# Fatar_Keyboard_TP8S_61Keys.net
KiCad netlist of a schematic drawn in EAGLE
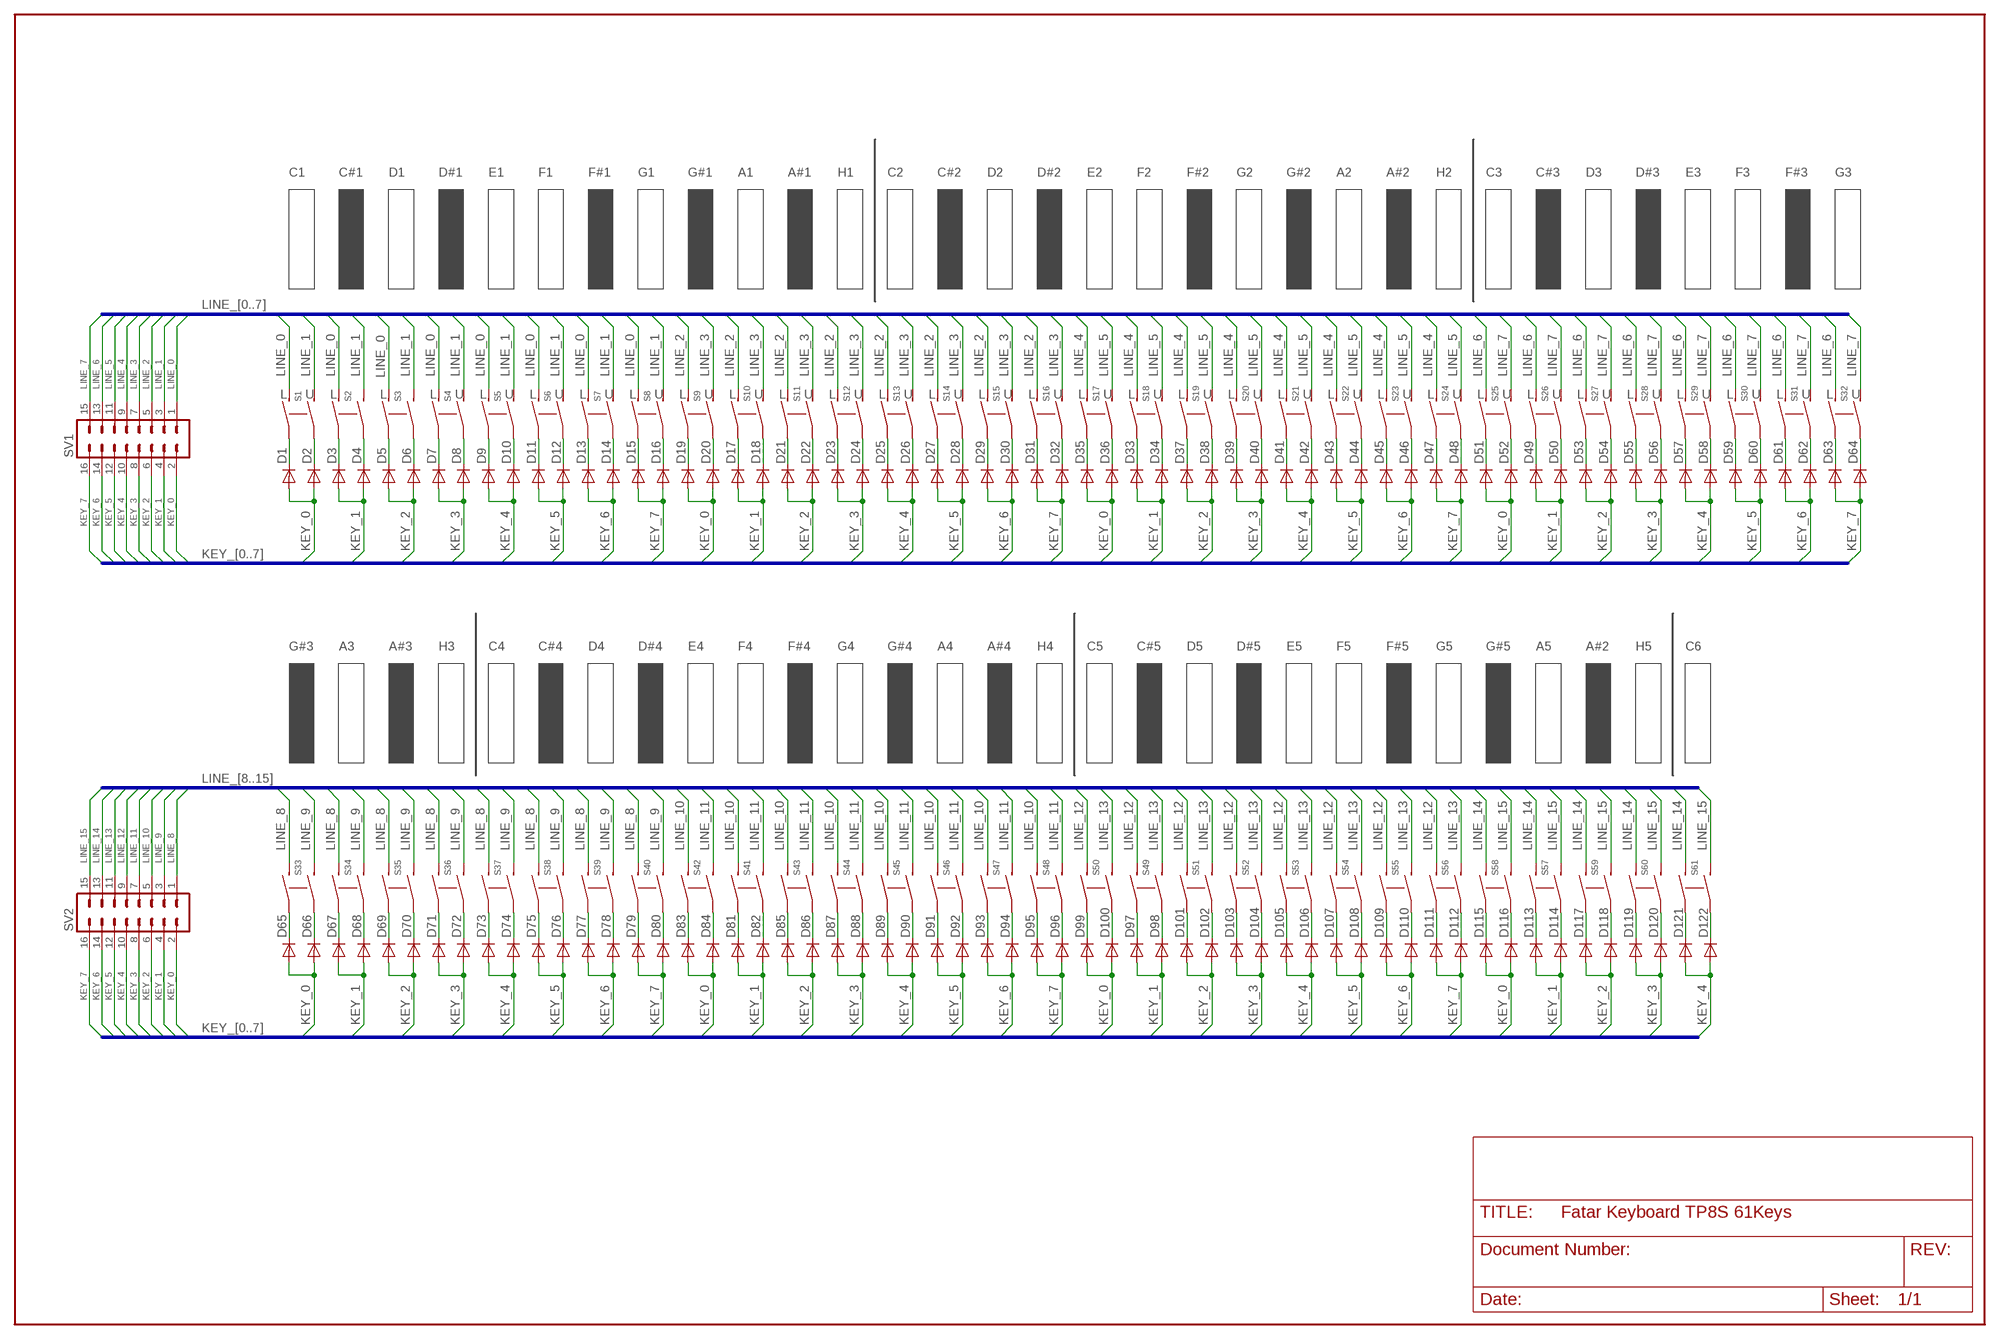
[diagram p0: schematic, sheet 1]

(export (version "E")
  (design (tool "Eeschema 10.0.6"))
  (components
    (comp (ref "D1")
      (value "1N4148DO35-7")
      (footprint "eagle-import:DO35-7")
      (libsource (lib "eagle-import") (part "1N4148DO35-7"))
    )
    (comp (ref "D2")
      (value "1N4148DO35-7")
      (footprint "eagle-import:DO35-7")
      (libsource (lib "eagle-import") (part "1N4148DO35-7"))
    )
    (comp (ref "D3")
      (value "1N4148DO35-7")
      (footprint "eagle-import:DO35-7")
      (libsource (lib "eagle-import") (part "1N4148DO35-7"))
    )
    (comp (ref "D4")
      (value "1N4148DO35-7")
      (footprint "eagle-import:DO35-7")
      (libsource (lib "eagle-import") (part "1N4148DO35-7"))
    )
    (comp (ref "D5")
      (value "1N4148DO35-7")
      (footprint "eagle-import:DO35-7")
      (libsource (lib "eagle-import") (part "1N4148DO35-7"))
    )
    (comp (ref "D6")
      (value "1N4148DO35-7")
      (footprint "eagle-import:DO35-7")
      (libsource (lib "eagle-import") (part "1N4148DO35-7"))
    )
    (comp (ref "D7")
      (value "1N4148DO35-7")
      (footprint "eagle-import:DO35-7")
      (libsource (lib "eagle-import") (part "1N4148DO35-7"))
    )
    (comp (ref "D8")
      (value "1N4148DO35-7")
      (footprint "eagle-import:DO35-7")
      (libsource (lib "eagle-import") (part "1N4148DO35-7"))
    )
    (comp (ref "D9")
      (value "1N4148DO35-7")
      (footprint "eagle-import:DO35-7")
      (libsource (lib "eagle-import") (part "1N4148DO35-7"))
    )
    (comp (ref "D10")
      (value "1N4148DO35-7")
      (footprint "eagle-import:DO35-7")
      (libsource (lib "eagle-import") (part "1N4148DO35-7"))
    )
    (comp (ref "D11")
      (value "1N4148DO35-7")
      (footprint "eagle-import:DO35-7")
      (libsource (lib "eagle-import") (part "1N4148DO35-7"))
    )
    (comp (ref "D12")
      (value "1N4148DO35-7")
      (footprint "eagle-import:DO35-7")
      (libsource (lib "eagle-import") (part "1N4148DO35-7"))
    )
    (comp (ref "D13")
      (value "1N4148DO35-7")
      (footprint "eagle-import:DO35-7")
      (libsource (lib "eagle-import") (part "1N4148DO35-7"))
    )
    (comp (ref "D14")
      (value "1N4148DO35-7")
      (footprint "eagle-import:DO35-7")
      (libsource (lib "eagle-import") (part "1N4148DO35-7"))
    )
    (comp (ref "D15")
      (value "1N4148DO35-7")
      (footprint "eagle-import:DO35-7")
      (libsource (lib "eagle-import") (part "1N4148DO35-7"))
    )
    (comp (ref "D16")
      (value "1N4148DO35-7")
      (footprint "eagle-import:DO35-7")
      (libsource (lib "eagle-import") (part "1N4148DO35-7"))
    )
    (comp (ref "D17")
      (value "1N4148DO35-7")
      (footprint "eagle-import:DO35-7")
      (libsource (lib "eagle-import") (part "1N4148DO35-7"))
    )
    (comp (ref "D18")
      (value "1N4148DO35-7")
      (footprint "eagle-import:DO35-7")
      (libsource (lib "eagle-import") (part "1N4148DO35-7"))
    )
    (comp (ref "D19")
      (value "1N4148DO35-7")
      (footprint "eagle-import:DO35-7")
      (libsource (lib "eagle-import") (part "1N4148DO35-7"))
    )
    (comp (ref "D20")
      (value "1N4148DO35-7")
      (footprint "eagle-import:DO35-7")
      (libsource (lib "eagle-import") (part "1N4148DO35-7"))
    )
    (comp (ref "D21")
      (value "1N4148DO35-7")
      (footprint "eagle-import:DO35-7")
      (libsource (lib "eagle-import") (part "1N4148DO35-7"))
    )
    (comp (ref "D22")
      (value "1N4148DO35-7")
      (footprint "eagle-import:DO35-7")
      (libsource (lib "eagle-import") (part "1N4148DO35-7"))
    )
    (comp (ref "D23")
      (value "1N4148DO35-7")
      (footprint "eagle-import:DO35-7")
      (libsource (lib "eagle-import") (part "1N4148DO35-7"))
    )
    (comp (ref "D24")
      (value "1N4148DO35-7")
      (footprint "eagle-import:DO35-7")
      (libsource (lib "eagle-import") (part "1N4148DO35-7"))
    )
    (comp (ref "D25")
      (value "1N4148DO35-7")
      (footprint "eagle-import:DO35-7")
      (libsource (lib "eagle-import") (part "1N4148DO35-7"))
    )
    (comp (ref "D26")
      (value "1N4148DO35-7")
      (footprint "eagle-import:DO35-7")
      (libsource (lib "eagle-import") (part "1N4148DO35-7"))
    )
    (comp (ref "D27")
      (value "1N4148DO35-7")
      (footprint "eagle-import:DO35-7")
      (libsource (lib "eagle-import") (part "1N4148DO35-7"))
    )
    (comp (ref "D28")
      (value "1N4148DO35-7")
      (footprint "eagle-import:DO35-7")
      (libsource (lib "eagle-import") (part "1N4148DO35-7"))
    )
    (comp (ref "D29")
      (value "1N4148DO35-7")
      (footprint "eagle-import:DO35-7")
      (libsource (lib "eagle-import") (part "1N4148DO35-7"))
    )
    (comp (ref "D30")
      (value "1N4148DO35-7")
      (footprint "eagle-import:DO35-7")
      (libsource (lib "eagle-import") (part "1N4148DO35-7"))
    )
    (comp (ref "D31")
      (value "1N4148DO35-7")
      (footprint "eagle-import:DO35-7")
      (libsource (lib "eagle-import") (part "1N4148DO35-7"))
    )
    (comp (ref "D32")
      (value "1N4148DO35-7")
      (footprint "eagle-import:DO35-7")
      (libsource (lib "eagle-import") (part "1N4148DO35-7"))
    )
    (comp (ref "D33")
      (value "1N4148DO35-7")
      (footprint "eagle-import:DO35-7")
      (libsource (lib "eagle-import") (part "1N4148DO35-7"))
    )
    (comp (ref "D34")
      (value "1N4148DO35-7")
      (footprint "eagle-import:DO35-7")
      (libsource (lib "eagle-import") (part "1N4148DO35-7"))
    )
    (comp (ref "D35")
      (value "1N4148DO35-7")
      (footprint "eagle-import:DO35-7")
      (libsource (lib "eagle-import") (part "1N4148DO35-7"))
    )
    (comp (ref "D36")
      (value "1N4148DO35-7")
      (footprint "eagle-import:DO35-7")
      (libsource (lib "eagle-import") (part "1N4148DO35-7"))
    )
    (comp (ref "D37")
      (value "1N4148DO35-7")
      (footprint "eagle-import:DO35-7")
      (libsource (lib "eagle-import") (part "1N4148DO35-7"))
    )
    (comp (ref "D38")
      (value "1N4148DO35-7")
      (footprint "eagle-import:DO35-7")
      (libsource (lib "eagle-import") (part "1N4148DO35-7"))
    )
    (comp (ref "D39")
      (value "1N4148DO35-7")
      (footprint "eagle-import:DO35-7")
      (libsource (lib "eagle-import") (part "1N4148DO35-7"))
    )
    (comp (ref "D40")
      (value "1N4148DO35-7")
      (footprint "eagle-import:DO35-7")
      (libsource (lib "eagle-import") (part "1N4148DO35-7"))
    )
    (comp (ref "D41")
      (value "1N4148DO35-7")
      (footprint "eagle-import:DO35-7")
      (libsource (lib "eagle-import") (part "1N4148DO35-7"))
    )
    (comp (ref "D42")
      (value "1N4148DO35-7")
      (footprint "eagle-import:DO35-7")
      (libsource (lib "eagle-import") (part "1N4148DO35-7"))
    )
    (comp (ref "D43")
      (value "1N4148DO35-7")
      (footprint "eagle-import:DO35-7")
      (libsource (lib "eagle-import") (part "1N4148DO35-7"))
    )
    (comp (ref "D44")
      (value "1N4148DO35-7")
      (footprint "eagle-import:DO35-7")
      (libsource (lib "eagle-import") (part "1N4148DO35-7"))
    )
    (comp (ref "D45")
      (value "1N4148DO35-7")
      (footprint "eagle-import:DO35-7")
      (libsource (lib "eagle-import") (part "1N4148DO35-7"))
    )
    (comp (ref "D46")
      (value "1N4148DO35-7")
      (footprint "eagle-import:DO35-7")
      (libsource (lib "eagle-import") (part "1N4148DO35-7"))
    )
    (comp (ref "D47")
      (value "1N4148DO35-7")
      (footprint "eagle-import:DO35-7")
      (libsource (lib "eagle-import") (part "1N4148DO35-7"))
    )
    (comp (ref "D48")
      (value "1N4148DO35-7")
      (footprint "eagle-import:DO35-7")
      (libsource (lib "eagle-import") (part "1N4148DO35-7"))
    )
    (comp (ref "D49")
      (value "1N4148DO35-7")
      (footprint "eagle-import:DO35-7")
      (libsource (lib "eagle-import") (part "1N4148DO35-7"))
    )
    (comp (ref "D50")
      (value "1N4148DO35-7")
      (footprint "eagle-import:DO35-7")
      (libsource (lib "eagle-import") (part "1N4148DO35-7"))
    )
    (comp (ref "D51")
      (value "1N4148DO35-7")
      (footprint "eagle-import:DO35-7")
      (libsource (lib "eagle-import") (part "1N4148DO35-7"))
    )
    (comp (ref "D52")
      (value "1N4148DO35-7")
      (footprint "eagle-import:DO35-7")
      (libsource (lib "eagle-import") (part "1N4148DO35-7"))
    )
    (comp (ref "D53")
      (value "1N4148DO35-7")
      (footprint "eagle-import:DO35-7")
      (libsource (lib "eagle-import") (part "1N4148DO35-7"))
    )
    (comp (ref "D54")
      (value "1N4148DO35-7")
      (footprint "eagle-import:DO35-7")
      (libsource (lib "eagle-import") (part "1N4148DO35-7"))
    )
    (comp (ref "D55")
      (value "1N4148DO35-7")
      (footprint "eagle-import:DO35-7")
      (libsource (lib "eagle-import") (part "1N4148DO35-7"))
    )
    (comp (ref "D56")
      (value "1N4148DO35-7")
      (footprint "eagle-import:DO35-7")
      (libsource (lib "eagle-import") (part "1N4148DO35-7"))
    )
    (comp (ref "D57")
      (value "1N4148DO35-7")
      (footprint "eagle-import:DO35-7")
      (libsource (lib "eagle-import") (part "1N4148DO35-7"))
    )
    (comp (ref "D58")
      (value "1N4148DO35-7")
      (footprint "eagle-import:DO35-7")
      (libsource (lib "eagle-import") (part "1N4148DO35-7"))
    )
    (comp (ref "D59")
      (value "1N4148DO35-7")
      (footprint "eagle-import:DO35-7")
      (libsource (lib "eagle-import") (part "1N4148DO35-7"))
    )
    (comp (ref "D60")
      (value "1N4148DO35-7")
      (footprint "eagle-import:DO35-7")
      (libsource (lib "eagle-import") (part "1N4148DO35-7"))
    )
    (comp (ref "D61")
      (value "1N4148DO35-7")
      (footprint "eagle-import:DO35-7")
      (libsource (lib "eagle-import") (part "1N4148DO35-7"))
    )
    (comp (ref "D62")
      (value "1N4148DO35-7")
      (footprint "eagle-import:DO35-7")
      (libsource (lib "eagle-import") (part "1N4148DO35-7"))
    )
    (comp (ref "D63")
      (value "1N4148DO35-7")
      (footprint "eagle-import:DO35-7")
      (libsource (lib "eagle-import") (part "1N4148DO35-7"))
    )
    (comp (ref "D64")
      (value "1N4148DO35-7")
      (footprint "eagle-import:DO35-7")
      (libsource (lib "eagle-import") (part "1N4148DO35-7"))
    )
    (comp (ref "D65")
      (value "1N4148DO35-7")
      (footprint "eagle-import:DO35-7")
      (libsource (lib "eagle-import") (part "1N4148DO35-7"))
    )
    (comp (ref "D66")
      (value "1N4148DO35-7")
      (footprint "eagle-import:DO35-7")
      (libsource (lib "eagle-import") (part "1N4148DO35-7"))
    )
    (comp (ref "D67")
      (value "1N4148DO35-7")
      (footprint "eagle-import:DO35-7")
      (libsource (lib "eagle-import") (part "1N4148DO35-7"))
    )
    (comp (ref "D68")
      (value "1N4148DO35-7")
      (footprint "eagle-import:DO35-7")
      (libsource (lib "eagle-import") (part "1N4148DO35-7"))
    )
    (comp (ref "D69")
      (value "1N4148DO35-7")
      (footprint "eagle-import:DO35-7")
      (libsource (lib "eagle-import") (part "1N4148DO35-7"))
    )
    (comp (ref "D70")
      (value "1N4148DO35-7")
      (footprint "eagle-import:DO35-7")
      (libsource (lib "eagle-import") (part "1N4148DO35-7"))
    )
    (comp (ref "D71")
      (value "1N4148DO35-7")
      (footprint "eagle-import:DO35-7")
      (libsource (lib "eagle-import") (part "1N4148DO35-7"))
    )
    (comp (ref "D72")
      (value "1N4148DO35-7")
      (footprint "eagle-import:DO35-7")
      (libsource (lib "eagle-import") (part "1N4148DO35-7"))
    )
    (comp (ref "D73")
      (value "1N4148DO35-7")
      (footprint "eagle-import:DO35-7")
      (libsource (lib "eagle-import") (part "1N4148DO35-7"))
    )
    (comp (ref "D74")
      (value "1N4148DO35-7")
      (footprint "eagle-import:DO35-7")
      (libsource (lib "eagle-import") (part "1N4148DO35-7"))
    )
    (comp (ref "D75")
      (value "1N4148DO35-7")
      (footprint "eagle-import:DO35-7")
      (libsource (lib "eagle-import") (part "1N4148DO35-7"))
    )
    (comp (ref "D76")
      (value "1N4148DO35-7")
      (footprint "eagle-import:DO35-7")
      (libsource (lib "eagle-import") (part "1N4148DO35-7"))
    )
    (comp (ref "D77")
      (value "1N4148DO35-7")
      (footprint "eagle-import:DO35-7")
      (libsource (lib "eagle-import") (part "1N4148DO35-7"))
    )
    (comp (ref "D78")
      (value "1N4148DO35-7")
      (footprint "eagle-import:DO35-7")
      (libsource (lib "eagle-import") (part "1N4148DO35-7"))
    )
    (comp (ref "D79")
      (value "1N4148DO35-7")
      (footprint "eagle-import:DO35-7")
      (libsource (lib "eagle-import") (part "1N4148DO35-7"))
    )
    (comp (ref "D80")
      (value "1N4148DO35-7")
      (footprint "eagle-import:DO35-7")
      (libsource (lib "eagle-import") (part "1N4148DO35-7"))
    )
    (comp (ref "D81")
      (value "1N4148DO35-7")
      (footprint "eagle-import:DO35-7")
      (libsource (lib "eagle-import") (part "1N4148DO35-7"))
    )
    (comp (ref "D82")
      (value "1N4148DO35-7")
      (footprint "eagle-import:DO35-7")
      (libsource (lib "eagle-import") (part "1N4148DO35-7"))
    )
    (comp (ref "D83")
      (value "1N4148DO35-7")
      (footprint "eagle-import:DO35-7")
      (libsource (lib "eagle-import") (part "1N4148DO35-7"))
    )
    (comp (ref "D84")
      (value "1N4148DO35-7")
      (footprint "eagle-import:DO35-7")
      (libsource (lib "eagle-import") (part "1N4148DO35-7"))
    )
    (comp (ref "D85")
      (value "1N4148DO35-7")
      (footprint "eagle-import:DO35-7")
      (libsource (lib "eagle-import") (part "1N4148DO35-7"))
    )
    (comp (ref "D86")
      (value "1N4148DO35-7")
      (footprint "eagle-import:DO35-7")
      (libsource (lib "eagle-import") (part "1N4148DO35-7"))
    )
    (comp (ref "D87")
      (value "1N4148DO35-7")
      (footprint "eagle-import:DO35-7")
      (libsource (lib "eagle-import") (part "1N4148DO35-7"))
    )
    (comp (ref "D88")
      (value "1N4148DO35-7")
      (footprint "eagle-import:DO35-7")
      (libsource (lib "eagle-import") (part "1N4148DO35-7"))
    )
    (comp (ref "D89")
      (value "1N4148DO35-7")
      (footprint "eagle-import:DO35-7")
      (libsource (lib "eagle-import") (part "1N4148DO35-7"))
    )
    (comp (ref "D90")
      (value "1N4148DO35-7")
      (footprint "eagle-import:DO35-7")
      (libsource (lib "eagle-import") (part "1N4148DO35-7"))
    )
    (comp (ref "D91")
      (value "1N4148DO35-7")
      (footprint "eagle-import:DO35-7")
      (libsource (lib "eagle-import") (part "1N4148DO35-7"))
    )
    (comp (ref "D92")
      (value "1N4148DO35-7")
      (footprint "eagle-import:DO35-7")
      (libsource (lib "eagle-import") (part "1N4148DO35-7"))
    )
    (comp (ref "D93")
      (value "1N4148DO35-7")
      (footprint "eagle-import:DO35-7")
      (libsource (lib "eagle-import") (part "1N4148DO35-7"))
    )
    (comp (ref "D94")
      (value "1N4148DO35-7")
      (footprint "eagle-import:DO35-7")
      (libsource (lib "eagle-import") (part "1N4148DO35-7"))
    )
    (comp (ref "D95")
      (value "1N4148DO35-7")
      (footprint "eagle-import:DO35-7")
      (libsource (lib "eagle-import") (part "1N4148DO35-7"))
    )
    (comp (ref "D96")
      (value "1N4148DO35-7")
      (footprint "eagle-import:DO35-7")
      (libsource (lib "eagle-import") (part "1N4148DO35-7"))
    )
    (comp (ref "D97")
      (value "1N4148DO35-7")
      (footprint "eagle-import:DO35-7")
      (libsource (lib "eagle-import") (part "1N4148DO35-7"))
    )
    (comp (ref "D98")
      (value "1N4148DO35-7")
      (footprint "eagle-import:DO35-7")
      (libsource (lib "eagle-import") (part "1N4148DO35-7"))
    )
    (comp (ref "D99")
      (value "1N4148DO35-7")
      (footprint "eagle-import:DO35-7")
      (libsource (lib "eagle-import") (part "1N4148DO35-7"))
    )
    (comp (ref "D100")
      (value "1N4148DO35-7")
      (footprint "eagle-import:DO35-7")
      (libsource (lib "eagle-import") (part "1N4148DO35-7"))
    )
    (comp (ref "D101")
      (value "1N4148DO35-7")
      (footprint "eagle-import:DO35-7")
      (libsource (lib "eagle-import") (part "1N4148DO35-7"))
    )
    (comp (ref "D102")
      (value "1N4148DO35-7")
      (footprint "eagle-import:DO35-7")
      (libsource (lib "eagle-import") (part "1N4148DO35-7"))
    )
    (comp (ref "D103")
      (value "1N4148DO35-7")
      (footprint "eagle-import:DO35-7")
      (libsource (lib "eagle-import") (part "1N4148DO35-7"))
    )
    (comp (ref "D104")
      (value "1N4148DO35-7")
      (footprint "eagle-import:DO35-7")
      (libsource (lib "eagle-import") (part "1N4148DO35-7"))
    )
    (comp (ref "D105")
      (value "1N4148DO35-7")
      (footprint "eagle-import:DO35-7")
      (libsource (lib "eagle-import") (part "1N4148DO35-7"))
    )
    (comp (ref "D106")
      (value "1N4148DO35-7")
      (footprint "eagle-import:DO35-7")
      (libsource (lib "eagle-import") (part "1N4148DO35-7"))
    )
    (comp (ref "D107")
      (value "1N4148DO35-7")
      (footprint "eagle-import:DO35-7")
      (libsource (lib "eagle-import") (part "1N4148DO35-7"))
    )
    (comp (ref "D108")
      (value "1N4148DO35-7")
      (footprint "eagle-import:DO35-7")
      (libsource (lib "eagle-import") (part "1N4148DO35-7"))
    )
    (comp (ref "D109")
      (value "1N4148DO35-7")
      (footprint "eagle-import:DO35-7")
      (libsource (lib "eagle-import") (part "1N4148DO35-7"))
    )
    (comp (ref "D110")
      (value "1N4148DO35-7")
      (footprint "eagle-import:DO35-7")
      (libsource (lib "eagle-import") (part "1N4148DO35-7"))
    )
    (comp (ref "D111")
      (value "1N4148DO35-7")
      (footprint "eagle-import:DO35-7")
      (libsource (lib "eagle-import") (part "1N4148DO35-7"))
    )
    (comp (ref "D112")
      (value "1N4148DO35-7")
      (footprint "eagle-import:DO35-7")
      (libsource (lib "eagle-import") (part "1N4148DO35-7"))
    )
    (comp (ref "D113")
      (value "1N4148DO35-7")
      (footprint "eagle-import:DO35-7")
      (libsource (lib "eagle-import") (part "1N4148DO35-7"))
    )
    (comp (ref "D114")
      (value "1N4148DO35-7")
      (footprint "eagle-import:DO35-7")
      (libsource (lib "eagle-import") (part "1N4148DO35-7"))
    )
    (comp (ref "D115")
      (value "1N4148DO35-7")
      (footprint "eagle-import:DO35-7")
      (libsource (lib "eagle-import") (part "1N4148DO35-7"))
    )
    (comp (ref "D116")
      (value "1N4148DO35-7")
      (footprint "eagle-import:DO35-7")
      (libsource (lib "eagle-import") (part "1N4148DO35-7"))
    )
    (comp (ref "D117")
      (value "1N4148DO35-7")
      (footprint "eagle-import:DO35-7")
      (libsource (lib "eagle-import") (part "1N4148DO35-7"))
    )
    (comp (ref "D118")
      (value "1N4148DO35-7")
      (footprint "eagle-import:DO35-7")
      (libsource (lib "eagle-import") (part "1N4148DO35-7"))
    )
    (comp (ref "D119")
      (value "1N4148DO35-7")
      (footprint "eagle-import:DO35-7")
      (libsource (lib "eagle-import") (part "1N4148DO35-7"))
    )
    (comp (ref "D120")
      (value "1N4148DO35-7")
      (footprint "eagle-import:DO35-7")
      (libsource (lib "eagle-import") (part "1N4148DO35-7"))
    )
    (comp (ref "D121")
      (value "1N4148DO35-7")
      (footprint "eagle-import:DO35-7")
      (libsource (lib "eagle-import") (part "1N4148DO35-7"))
    )
    (comp (ref "D122")
      (value "1N4148DO35-7")
      (footprint "eagle-import:DO35-7")
      (libsource (lib "eagle-import") (part "1N4148DO35-7"))
    )
    (comp (ref "S1")
      (value "PVA1")
      (footprint "eagle-import:PVA1F")
      (libsource (lib "eagle-import") (part "PVA1"))
    )
    (comp (ref "S2")
      (value "PVA1")
      (footprint "eagle-import:PVA1F")
      (libsource (lib "eagle-import") (part "PVA1"))
    )
    (comp (ref "S3")
      (value "PVA1")
      (footprint "eagle-import:PVA1F")
      (libsource (lib "eagle-import") (part "PVA1"))
    )
    (comp (ref "S4")
      (value "PVA1")
      (footprint "eagle-import:PVA1F")
      (libsource (lib "eagle-import") (part "PVA1"))
    )
    (comp (ref "S5")
      (value "PVA1")
      (footprint "eagle-import:PVA1F")
      (libsource (lib "eagle-import") (part "PVA1"))
    )
    (comp (ref "S6")
      (value "PVA1")
      (footprint "eagle-import:PVA1F")
      (libsource (lib "eagle-import") (part "PVA1"))
    )
    (comp (ref "S7")
      (value "PVA1")
      (footprint "eagle-import:PVA1F")
      (libsource (lib "eagle-import") (part "PVA1"))
    )
    (comp (ref "S8")
      (value "PVA1")
      (footprint "eagle-import:PVA1F")
      (libsource (lib "eagle-import") (part "PVA1"))
    )
    (comp (ref "S9")
      (value "PVA1")
      (footprint "eagle-import:PVA1F")
      (libsource (lib "eagle-import") (part "PVA1"))
    )
    (comp (ref "S10")
      (value "PVA1")
      (footprint "eagle-import:PVA1F")
      (libsource (lib "eagle-import") (part "PVA1"))
    )
    (comp (ref "S11")
      (value "PVA1")
      (footprint "eagle-import:PVA1F")
      (libsource (lib "eagle-import") (part "PVA1"))
    )
    (comp (ref "S12")
      (value "PVA1")
      (footprint "eagle-import:PVA1F")
      (libsource (lib "eagle-import") (part "PVA1"))
    )
    (comp (ref "S13")
      (value "PVA1")
      (footprint "eagle-import:PVA1F")
      (libsource (lib "eagle-import") (part "PVA1"))
    )
    (comp (ref "S14")
      (value "PVA1")
      (footprint "eagle-import:PVA1F")
      (libsource (lib "eagle-import") (part "PVA1"))
    )
    (comp (ref "S15")
      (value "PVA1")
      (footprint "eagle-import:PVA1F")
      (libsource (lib "eagle-import") (part "PVA1"))
    )
    (comp (ref "S16")
      (value "PVA1")
      (footprint "eagle-import:PVA1F")
      (libsource (lib "eagle-import") (part "PVA1"))
    )
    (comp (ref "S17")
      (value "PVA1")
      (footprint "eagle-import:PVA1F")
      (libsource (lib "eagle-import") (part "PVA1"))
    )
    (comp (ref "S18")
      (value "PVA1")
      (footprint "eagle-import:PVA1F")
      (libsource (lib "eagle-import") (part "PVA1"))
    )
    (comp (ref "S19")
      (value "PVA1")
      (footprint "eagle-import:PVA1F")
      (libsource (lib "eagle-import") (part "PVA1"))
    )
    (comp (ref "S20")
      (value "PVA1")
      (footprint "eagle-import:PVA1F")
      (libsource (lib "eagle-import") (part "PVA1"))
    )
    (comp (ref "S21")
      (value "PVA1")
      (footprint "eagle-import:PVA1F")
      (libsource (lib "eagle-import") (part "PVA1"))
    )
    (comp (ref "S22")
      (value "PVA1")
      (footprint "eagle-import:PVA1F")
      (libsource (lib "eagle-import") (part "PVA1"))
    )
    (comp (ref "S23")
      (value "PVA1")
      (footprint "eagle-import:PVA1F")
      (libsource (lib "eagle-import") (part "PVA1"))
    )
    (comp (ref "S24")
      (value "PVA1")
      (footprint "eagle-import:PVA1F")
      (libsource (lib "eagle-import") (part "PVA1"))
    )
    (comp (ref "S25")
      (value "PVA1")
      (footprint "eagle-import:PVA1F")
      (libsource (lib "eagle-import") (part "PVA1"))
    )
    (comp (ref "S26")
      (value "PVA1")
      (footprint "eagle-import:PVA1F")
      (libsource (lib "eagle-import") (part "PVA1"))
    )
    (comp (ref "S27")
      (value "PVA1")
      (footprint "eagle-import:PVA1F")
      (libsource (lib "eagle-import") (part "PVA1"))
    )
    (comp (ref "S28")
      (value "PVA1")
      (footprint "eagle-import:PVA1F")
      (libsource (lib "eagle-import") (part "PVA1"))
    )
    (comp (ref "S29")
      (value "PVA1")
      (footprint "eagle-import:PVA1F")
      (libsource (lib "eagle-import") (part "PVA1"))
    )
    (comp (ref "S30")
      (value "PVA1")
      (footprint "eagle-import:PVA1F")
      (libsource (lib "eagle-import") (part "PVA1"))
    )
    (comp (ref "S31")
      (value "PVA1")
      (footprint "eagle-import:PVA1F")
      (libsource (lib "eagle-import") (part "PVA1"))
    )
    (comp (ref "S32")
      (value "PVA1")
      (footprint "eagle-import:PVA1F")
      (libsource (lib "eagle-import") (part "PVA1"))
    )
    (comp (ref "S33")
      (value "PVA1")
      (footprint "eagle-import:PVA1F")
      (libsource (lib "eagle-import") (part "PVA1"))
    )
    (comp (ref "S34")
      (value "PVA1")
      (footprint "eagle-import:PVA1F")
      (libsource (lib "eagle-import") (part "PVA1"))
    )
    (comp (ref "S35")
      (value "PVA1")
      (footprint "eagle-import:PVA1F")
      (libsource (lib "eagle-import") (part "PVA1"))
    )
    (comp (ref "S36")
      (value "PVA1")
      (footprint "eagle-import:PVA1F")
      (libsource (lib "eagle-import") (part "PVA1"))
    )
    (comp (ref "S37")
      (value "PVA1")
      (footprint "eagle-import:PVA1F")
      (libsource (lib "eagle-import") (part "PVA1"))
    )
    (comp (ref "S38")
      (value "PVA1")
      (footprint "eagle-import:PVA1F")
      (libsource (lib "eagle-import") (part "PVA1"))
    )
    (comp (ref "S39")
      (value "PVA1")
      (footprint "eagle-import:PVA1F")
      (libsource (lib "eagle-import") (part "PVA1"))
    )
    (comp (ref "S40")
      (value "PVA1")
      (footprint "eagle-import:PVA1F")
      (libsource (lib "eagle-import") (part "PVA1"))
    )
    (comp (ref "S41")
      (value "PVA1")
      (footprint "eagle-import:PVA1F")
      (libsource (lib "eagle-import") (part "PVA1"))
    )
    (comp (ref "S42")
      (value "PVA1")
      (footprint "eagle-import:PVA1F")
      (libsource (lib "eagle-import") (part "PVA1"))
    )
    (comp (ref "S43")
      (value "PVA1")
      (footprint "eagle-import:PVA1F")
      (libsource (lib "eagle-import") (part "PVA1"))
    )
    (comp (ref "S44")
      (value "PVA1")
      (footprint "eagle-import:PVA1F")
      (libsource (lib "eagle-import") (part "PVA1"))
    )
    (comp (ref "S45")
      (value "PVA1")
      (footprint "eagle-import:PVA1F")
      (libsource (lib "eagle-import") (part "PVA1"))
    )
    (comp (ref "S46")
      (value "PVA1")
      (footprint "eagle-import:PVA1F")
      (libsource (lib "eagle-import") (part "PVA1"))
    )
    (comp (ref "S47")
      (value "PVA1")
      (footprint "eagle-import:PVA1F")
      (libsource (lib "eagle-import") (part "PVA1"))
    )
    (comp (ref "S48")
      (value "PVA1")
      (footprint "eagle-import:PVA1F")
      (libsource (lib "eagle-import") (part "PVA1"))
    )
    (comp (ref "S49")
      (value "PVA1")
      (footprint "eagle-import:PVA1F")
      (libsource (lib "eagle-import") (part "PVA1"))
    )
    (comp (ref "S50")
      (value "PVA1")
      (footprint "eagle-import:PVA1F")
      (libsource (lib "eagle-import") (part "PVA1"))
    )
    (comp (ref "S51")
      (value "PVA1")
      (footprint "eagle-import:PVA1F")
      (libsource (lib "eagle-import") (part "PVA1"))
    )
    (comp (ref "S52")
      (value "PVA1")
      (footprint "eagle-import:PVA1F")
      (libsource (lib "eagle-import") (part "PVA1"))
    )
    (comp (ref "S53")
      (value "PVA1")
      (footprint "eagle-import:PVA1F")
      (libsource (lib "eagle-import") (part "PVA1"))
    )
    (comp (ref "S54")
      (value "PVA1")
      (footprint "eagle-import:PVA1F")
      (libsource (lib "eagle-import") (part "PVA1"))
    )
    (comp (ref "S55")
      (value "PVA1")
      (footprint "eagle-import:PVA1F")
      (libsource (lib "eagle-import") (part "PVA1"))
    )
    (comp (ref "S56")
      (value "PVA1")
      (footprint "eagle-import:PVA1F")
      (libsource (lib "eagle-import") (part "PVA1"))
    )
    (comp (ref "S57")
      (value "PVA1")
      (footprint "eagle-import:PVA1F")
      (libsource (lib "eagle-import") (part "PVA1"))
    )
    (comp (ref "S58")
      (value "PVA1")
      (footprint "eagle-import:PVA1F")
      (libsource (lib "eagle-import") (part "PVA1"))
    )
    (comp (ref "S59")
      (value "PVA1")
      (footprint "eagle-import:PVA1F")
      (libsource (lib "eagle-import") (part "PVA1"))
    )
    (comp (ref "S60")
      (value "PVA1")
      (footprint "eagle-import:PVA1F")
      (libsource (lib "eagle-import") (part "PVA1"))
    )
    (comp (ref "S61")
      (value "PVA1")
      (footprint "eagle-import:PVA1F")
      (libsource (lib "eagle-import") (part "PVA1"))
    )
    (comp (ref "SV1")
      (value "ML16")
      (footprint "eagle-import:ML16")
      (libsource (lib "eagle-import") (part "ML16"))
    )
    (comp (ref "SV2")
      (value "ML16")
      (footprint "eagle-import:ML16")
      (libsource (lib "eagle-import") (part "ML16"))
    )
  )
  (nets
    (net (code "1") (name "/KEY_0") (class "Default")
      (node (ref "D1") (pin "A") (pinfunction "A_A") (pintype "passive"))
      (node (ref "D100") (pin "A") (pinfunction "A_A") (pintype "passive"))
      (node (ref "D115") (pin "A") (pinfunction "A_A") (pintype "passive"))
      (node (ref "D116") (pin "A") (pinfunction "A_A") (pintype "passive"))
      (node (ref "D19") (pin "A") (pinfunction "A_A") (pintype "passive"))
      (node (ref "D2") (pin "A") (pinfunction "A_A") (pintype "passive"))
      (node (ref "D20") (pin "A") (pinfunction "A_A") (pintype "passive"))
      (node (ref "D35") (pin "A") (pinfunction "A_A") (pintype "passive"))
      (node (ref "D36") (pin "A") (pinfunction "A_A") (pintype "passive"))
      (node (ref "D51") (pin "A") (pinfunction "A_A") (pintype "passive"))
      (node (ref "D52") (pin "A") (pinfunction "A_A") (pintype "passive"))
      (node (ref "D65") (pin "A") (pinfunction "A_A") (pintype "passive"))
      (node (ref "D66") (pin "A") (pinfunction "A_A") (pintype "passive"))
      (node (ref "D83") (pin "A") (pinfunction "A_A") (pintype "passive"))
      (node (ref "D84") (pin "A") (pinfunction "A_A") (pintype "passive"))
      (node (ref "D99") (pin "A") (pinfunction "A_A") (pintype "passive"))
      (node (ref "SV1") (pin "2") (pinfunction "2_2") (pintype "passive"))
      (node (ref "SV2") (pin "2") (pinfunction "2_2") (pintype "passive"))
    )
    (net (code "2") (name "/KEY_1") (class "Default")
      (node (ref "D113") (pin "A") (pinfunction "A_A") (pintype "passive"))
      (node (ref "D114") (pin "A") (pinfunction "A_A") (pintype "passive"))
      (node (ref "D17") (pin "A") (pinfunction "A_A") (pintype "passive"))
      (node (ref "D18") (pin "A") (pinfunction "A_A") (pintype "passive"))
      (node (ref "D3") (pin "A") (pinfunction "A_A") (pintype "passive"))
      (node (ref "D33") (pin "A") (pinfunction "A_A") (pintype "passive"))
      (node (ref "D34") (pin "A") (pinfunction "A_A") (pintype "passive"))
      (node (ref "D4") (pin "A") (pinfunction "A_A") (pintype "passive"))
      (node (ref "D49") (pin "A") (pinfunction "A_A") (pintype "passive"))
      (node (ref "D50") (pin "A") (pinfunction "A_A") (pintype "passive"))
      (node (ref "D67") (pin "A") (pinfunction "A_A") (pintype "passive"))
      (node (ref "D68") (pin "A") (pinfunction "A_A") (pintype "passive"))
      (node (ref "D81") (pin "A") (pinfunction "A_A") (pintype "passive"))
      (node (ref "D82") (pin "A") (pinfunction "A_A") (pintype "passive"))
      (node (ref "D97") (pin "A") (pinfunction "A_A") (pintype "passive"))
      (node (ref "D98") (pin "A") (pinfunction "A_A") (pintype "passive"))
      (node (ref "SV1") (pin "4") (pinfunction "4_4") (pintype "passive"))
      (node (ref "SV2") (pin "4") (pinfunction "4_4") (pintype "passive"))
    )
    (net (code "3") (name "/KEY_2") (class "Default")
      (node (ref "D101") (pin "A") (pinfunction "A_A") (pintype "passive"))
      (node (ref "D102") (pin "A") (pinfunction "A_A") (pintype "passive"))
      (node (ref "D117") (pin "A") (pinfunction "A_A") (pintype "passive"))
      (node (ref "D118") (pin "A") (pinfunction "A_A") (pintype "passive"))
      (node (ref "D21") (pin "A") (pinfunction "A_A") (pintype "passive"))
      (node (ref "D22") (pin "A") (pinfunction "A_A") (pintype "passive"))
      (node (ref "D37") (pin "A") (pinfunction "A_A") (pintype "passive"))
      (node (ref "D38") (pin "A") (pinfunction "A_A") (pintype "passive"))
      (node (ref "D5") (pin "A") (pinfunction "A_A") (pintype "passive"))
      (node (ref "D53") (pin "A") (pinfunction "A_A") (pintype "passive"))
      (node (ref "D54") (pin "A") (pinfunction "A_A") (pintype "passive"))
      (node (ref "D6") (pin "A") (pinfunction "A_A") (pintype "passive"))
      (node (ref "D69") (pin "A") (pinfunction "A_A") (pintype "passive"))
      (node (ref "D70") (pin "A") (pinfunction "A_A") (pintype "passive"))
      (node (ref "D85") (pin "A") (pinfunction "A_A") (pintype "passive"))
      (node (ref "D86") (pin "A") (pinfunction "A_A") (pintype "passive"))
      (node (ref "SV1") (pin "6") (pinfunction "6_6") (pintype "passive"))
      (node (ref "SV2") (pin "6") (pinfunction "6_6") (pintype "passive"))
    )
    (net (code "4") (name "/KEY_3") (class "Default")
      (node (ref "D103") (pin "A") (pinfunction "A_A") (pintype "passive"))
      (node (ref "D104") (pin "A") (pinfunction "A_A") (pintype "passive"))
      (node (ref "D119") (pin "A") (pinfunction "A_A") (pintype "passive"))
      (node (ref "D120") (pin "A") (pinfunction "A_A") (pintype "passive"))
      (node (ref "D23") (pin "A") (pinfunction "A_A") (pintype "passive"))
      (node (ref "D24") (pin "A") (pinfunction "A_A") (pintype "passive"))
      (node (ref "D39") (pin "A") (pinfunction "A_A") (pintype "passive"))
      (node (ref "D40") (pin "A") (pinfunction "A_A") (pintype "passive"))
      (node (ref "D55") (pin "A") (pinfunction "A_A") (pintype "passive"))
      (node (ref "D56") (pin "A") (pinfunction "A_A") (pintype "passive"))
      (node (ref "D7") (pin "A") (pinfunction "A_A") (pintype "passive"))
      (node (ref "D71") (pin "A") (pinfunction "A_A") (pintype "passive"))
      (node (ref "D72") (pin "A") (pinfunction "A_A") (pintype "passive"))
      (node (ref "D8") (pin "A") (pinfunction "A_A") (pintype "passive"))
      (node (ref "D87") (pin "A") (pinfunction "A_A") (pintype "passive"))
      (node (ref "D88") (pin "A") (pinfunction "A_A") (pintype "passive"))
      (node (ref "SV1") (pin "8") (pinfunction "8_8") (pintype "passive"))
      (node (ref "SV2") (pin "8") (pinfunction "8_8") (pintype "passive"))
    )
    (net (code "5") (name "/KEY_4") (class "Default")
      (node (ref "D10") (pin "A") (pinfunction "A_A") (pintype "passive"))
      (node (ref "D105") (pin "A") (pinfunction "A_A") (pintype "passive"))
      (node (ref "D106") (pin "A") (pinfunction "A_A") (pintype "passive"))
      (node (ref "D121") (pin "A") (pinfunction "A_A") (pintype "passive"))
      (node (ref "D122") (pin "A") (pinfunction "A_A") (pintype "passive"))
      (node (ref "D25") (pin "A") (pinfunction "A_A") (pintype "passive"))
      (node (ref "D26") (pin "A") (pinfunction "A_A") (pintype "passive"))
      (node (ref "D41") (pin "A") (pinfunction "A_A") (pintype "passive"))
      (node (ref "D42") (pin "A") (pinfunction "A_A") (pintype "passive"))
      (node (ref "D57") (pin "A") (pinfunction "A_A") (pintype "passive"))
      (node (ref "D58") (pin "A") (pinfunction "A_A") (pintype "passive"))
      (node (ref "D73") (pin "A") (pinfunction "A_A") (pintype "passive"))
      (node (ref "D74") (pin "A") (pinfunction "A_A") (pintype "passive"))
      (node (ref "D89") (pin "A") (pinfunction "A_A") (pintype "passive"))
      (node (ref "D9") (pin "A") (pinfunction "A_A") (pintype "passive"))
      (node (ref "D90") (pin "A") (pinfunction "A_A") (pintype "passive"))
      (node (ref "SV1") (pin "10") (pinfunction "10_10") (pintype "passive"))
      (node (ref "SV2") (pin "10") (pinfunction "10_10") (pintype "passive"))
    )
    (net (code "6") (name "/KEY_5") (class "Default")
      (node (ref "D107") (pin "A") (pinfunction "A_A") (pintype "passive"))
      (node (ref "D108") (pin "A") (pinfunction "A_A") (pintype "passive"))
      (node (ref "D11") (pin "A") (pinfunction "A_A") (pintype "passive"))
      (node (ref "D12") (pin "A") (pinfunction "A_A") (pintype "passive"))
      (node (ref "D27") (pin "A") (pinfunction "A_A") (pintype "passive"))
      (node (ref "D28") (pin "A") (pinfunction "A_A") (pintype "passive"))
      (node (ref "D43") (pin "A") (pinfunction "A_A") (pintype "passive"))
      (node (ref "D44") (pin "A") (pinfunction "A_A") (pintype "passive"))
      (node (ref "D59") (pin "A") (pinfunction "A_A") (pintype "passive"))
      (node (ref "D60") (pin "A") (pinfunction "A_A") (pintype "passive"))
      (node (ref "D75") (pin "A") (pinfunction "A_A") (pintype "passive"))
      (node (ref "D76") (pin "A") (pinfunction "A_A") (pintype "passive"))
      (node (ref "D91") (pin "A") (pinfunction "A_A") (pintype "passive"))
      (node (ref "D92") (pin "A") (pinfunction "A_A") (pintype "passive"))
      (node (ref "SV1") (pin "12") (pinfunction "12_12") (pintype "passive"))
      (node (ref "SV2") (pin "12") (pinfunction "12_12") (pintype "passive"))
    )
    (net (code "7") (name "/KEY_6") (class "Default")
      (node (ref "D109") (pin "A") (pinfunction "A_A") (pintype "passive"))
      (node (ref "D110") (pin "A") (pinfunction "A_A") (pintype "passive"))
      (node (ref "D13") (pin "A") (pinfunction "A_A") (pintype "passive"))
      (node (ref "D14") (pin "A") (pinfunction "A_A") (pintype "passive"))
      (node (ref "D29") (pin "A") (pinfunction "A_A") (pintype "passive"))
      (node (ref "D30") (pin "A") (pinfunction "A_A") (pintype "passive"))
      (node (ref "D45") (pin "A") (pinfunction "A_A") (pintype "passive"))
      (node (ref "D46") (pin "A") (pinfunction "A_A") (pintype "passive"))
      (node (ref "D61") (pin "A") (pinfunction "A_A") (pintype "passive"))
      (node (ref "D62") (pin "A") (pinfunction "A_A") (pintype "passive"))
      (node (ref "D77") (pin "A") (pinfunction "A_A") (pintype "passive"))
      (node (ref "D78") (pin "A") (pinfunction "A_A") (pintype "passive"))
      (node (ref "D93") (pin "A") (pinfunction "A_A") (pintype "passive"))
      (node (ref "D94") (pin "A") (pinfunction "A_A") (pintype "passive"))
      (node (ref "SV1") (pin "14") (pinfunction "14_14") (pintype "passive"))
      (node (ref "SV2") (pin "14") (pinfunction "14_14") (pintype "passive"))
    )
    (net (code "8") (name "/KEY_7") (class "Default")
      (node (ref "D111") (pin "A") (pinfunction "A_A") (pintype "passive"))
      (node (ref "D112") (pin "A") (pinfunction "A_A") (pintype "passive"))
      (node (ref "D15") (pin "A") (pinfunction "A_A") (pintype "passive"))
      (node (ref "D16") (pin "A") (pinfunction "A_A") (pintype "passive"))
      (node (ref "D31") (pin "A") (pinfunction "A_A") (pintype "passive"))
      (node (ref "D32") (pin "A") (pinfunction "A_A") (pintype "passive"))
      (node (ref "D47") (pin "A") (pinfunction "A_A") (pintype "passive"))
      (node (ref "D48") (pin "A") (pinfunction "A_A") (pintype "passive"))
      (node (ref "D63") (pin "A") (pinfunction "A_A") (pintype "passive"))
      (node (ref "D64") (pin "A") (pinfunction "A_A") (pintype "passive"))
      (node (ref "D79") (pin "A") (pinfunction "A_A") (pintype "passive"))
      (node (ref "D80") (pin "A") (pinfunction "A_A") (pintype "passive"))
      (node (ref "D95") (pin "A") (pinfunction "A_A") (pintype "passive"))
      (node (ref "D96") (pin "A") (pinfunction "A_A") (pintype "passive"))
      (node (ref "SV1") (pin "16") (pinfunction "16_16") (pintype "passive"))
      (node (ref "SV2") (pin "16") (pinfunction "16_16") (pintype "passive"))
    )
    (net (code "10") (name "/LINE_0") (class "Default")
      (node (ref "S1") (pin "4") (pinfunction "S1_4") (pintype "passive"))
      (node (ref "S2") (pin "4") (pinfunction "S1_4") (pintype "passive"))
      (node (ref "S3") (pin "4") (pinfunction "S1_4") (pintype "passive"))
      (node (ref "S4") (pin "4") (pinfunction "S1_4") (pintype "passive"))
      (node (ref "S5") (pin "4") (pinfunction "S1_4") (pintype "passive"))
      (node (ref "S6") (pin "4") (pinfunction "S1_4") (pintype "passive"))
      (node (ref "S7") (pin "4") (pinfunction "S1_4") (pintype "passive"))
      (node (ref "S8") (pin "4") (pinfunction "S1_4") (pintype "passive"))
      (node (ref "SV1") (pin "1") (pinfunction "1_1") (pintype "passive"))
    )
    (net (code "11") (name "/LINE_1") (class "Default")
      (node (ref "S1") (pin "3") (pinfunction "S_3") (pintype "passive"))
      (node (ref "S2") (pin "3") (pinfunction "S_3") (pintype "passive"))
      (node (ref "S3") (pin "3") (pinfunction "S_3") (pintype "passive"))
      (node (ref "S4") (pin "3") (pinfunction "S_3") (pintype "passive"))
      (node (ref "S5") (pin "3") (pinfunction "S_3") (pintype "passive"))
      (node (ref "S6") (pin "3") (pinfunction "S_3") (pintype "passive"))
      (node (ref "S7") (pin "3") (pinfunction "S_3") (pintype "passive"))
      (node (ref "S8") (pin "3") (pinfunction "S_3") (pintype "passive"))
      (node (ref "SV1") (pin "3") (pinfunction "3_3") (pintype "passive"))
    )
    (net (code "12") (name "/LINE_2") (class "Default")
      (node (ref "S10") (pin "4") (pinfunction "S1_4") (pintype "passive"))
      (node (ref "S11") (pin "4") (pinfunction "S1_4") (pintype "passive"))
      (node (ref "S12") (pin "4") (pinfunction "S1_4") (pintype "passive"))
      (node (ref "S13") (pin "4") (pinfunction "S1_4") (pintype "passive"))
      (node (ref "S14") (pin "4") (pinfunction "S1_4") (pintype "passive"))
      (node (ref "S15") (pin "4") (pinfunction "S1_4") (pintype "passive"))
      (node (ref "S16") (pin "4") (pinfunction "S1_4") (pintype "passive"))
      (node (ref "S9") (pin "4") (pinfunction "S1_4") (pintype "passive"))
      (node (ref "SV1") (pin "5") (pinfunction "5_5") (pintype "passive"))
    )
    (net (code "13") (name "/LINE_3") (class "Default")
      (node (ref "S10") (pin "3") (pinfunction "S_3") (pintype "passive"))
      (node (ref "S11") (pin "3") (pinfunction "S_3") (pintype "passive"))
      (node (ref "S12") (pin "3") (pinfunction "S_3") (pintype "passive"))
      (node (ref "S13") (pin "3") (pinfunction "S_3") (pintype "passive"))
      (node (ref "S14") (pin "3") (pinfunction "S_3") (pintype "passive"))
      (node (ref "S15") (pin "3") (pinfunction "S_3") (pintype "passive"))
      (node (ref "S16") (pin "3") (pinfunction "S_3") (pintype "passive"))
      (node (ref "S9") (pin "3") (pinfunction "S_3") (pintype "passive"))
      (node (ref "SV1") (pin "7") (pinfunction "7_7") (pintype "passive"))
    )
    (net (code "14") (name "/LINE_4") (class "Default")
      (node (ref "S17") (pin "4") (pinfunction "S1_4") (pintype "passive"))
      (node (ref "S18") (pin "4") (pinfunction "S1_4") (pintype "passive"))
      (node (ref "S19") (pin "4") (pinfunction "S1_4") (pintype "passive"))
      (node (ref "S20") (pin "4") (pinfunction "S1_4") (pintype "passive"))
      (node (ref "S21") (pin "4") (pinfunction "S1_4") (pintype "passive"))
      (node (ref "S22") (pin "4") (pinfunction "S1_4") (pintype "passive"))
      (node (ref "S23") (pin "4") (pinfunction "S1_4") (pintype "passive"))
      (node (ref "S24") (pin "4") (pinfunction "S1_4") (pintype "passive"))
      (node (ref "SV1") (pin "9") (pinfunction "9_9") (pintype "passive"))
    )
    (net (code "15") (name "/LINE_5") (class "Default")
      (node (ref "S17") (pin "3") (pinfunction "S_3") (pintype "passive"))
      (node (ref "S18") (pin "3") (pinfunction "S_3") (pintype "passive"))
      (node (ref "S19") (pin "3") (pinfunction "S_3") (pintype "passive"))
      (node (ref "S20") (pin "3") (pinfunction "S_3") (pintype "passive"))
      (node (ref "S21") (pin "3") (pinfunction "S_3") (pintype "passive"))
      (node (ref "S22") (pin "3") (pinfunction "S_3") (pintype "passive"))
      (node (ref "S23") (pin "3") (pinfunction "S_3") (pintype "passive"))
      (node (ref "S24") (pin "3") (pinfunction "S_3") (pintype "passive"))
      (node (ref "SV1") (pin "11") (pinfunction "11_11") (pintype "passive"))
    )
    (net (code "16") (name "/LINE_6") (class "Default")
      (node (ref "S25") (pin "4") (pinfunction "S1_4") (pintype "passive"))
      (node (ref "S26") (pin "4") (pinfunction "S1_4") (pintype "passive"))
      (node (ref "S27") (pin "4") (pinfunction "S1_4") (pintype "passive"))
      (node (ref "S28") (pin "4") (pinfunction "S1_4") (pintype "passive"))
      (node (ref "S29") (pin "4") (pinfunction "S1_4") (pintype "passive"))
      (node (ref "S30") (pin "4") (pinfunction "S1_4") (pintype "passive"))
      (node (ref "S31") (pin "4") (pinfunction "S1_4") (pintype "passive"))
      (node (ref "S32") (pin "4") (pinfunction "S1_4") (pintype "passive"))
      (node (ref "SV1") (pin "13") (pinfunction "13_13") (pintype "passive"))
    )
    (net (code "17") (name "/LINE_7") (class "Default")
      (node (ref "S25") (pin "3") (pinfunction "S_3") (pintype "passive"))
      (node (ref "S26") (pin "3") (pinfunction "S_3") (pintype "passive"))
      (node (ref "S27") (pin "3") (pinfunction "S_3") (pintype "passive"))
      (node (ref "S28") (pin "3") (pinfunction "S_3") (pintype "passive"))
      (node (ref "S29") (pin "3") (pinfunction "S_3") (pintype "passive"))
      (node (ref "S30") (pin "3") (pinfunction "S_3") (pintype "passive"))
      (node (ref "S31") (pin "3") (pinfunction "S_3") (pintype "passive"))
      (node (ref "S32") (pin "3") (pinfunction "S_3") (pintype "passive"))
      (node (ref "SV1") (pin "15") (pinfunction "15_15") (pintype "passive"))
    )
    (net (code "18") (name "/LINE_8") (class "Default")
      (node (ref "S33") (pin "4") (pinfunction "S1_4") (pintype "passive"))
      (node (ref "S34") (pin "4") (pinfunction "S1_4") (pintype "passive"))
      (node (ref "S35") (pin "4") (pinfunction "S1_4") (pintype "passive"))
      (node (ref "S36") (pin "4") (pinfunction "S1_4") (pintype "passive"))
      (node (ref "S37") (pin "4") (pinfunction "S1_4") (pintype "passive"))
      (node (ref "S38") (pin "4") (pinfunction "S1_4") (pintype "passive"))
      (node (ref "S39") (pin "4") (pinfunction "S1_4") (pintype "passive"))
      (node (ref "S40") (pin "4") (pinfunction "S1_4") (pintype "passive"))
      (node (ref "SV2") (pin "1") (pinfunction "1_1") (pintype "passive"))
    )
    (net (code "19") (name "/LINE_9") (class "Default")
      (node (ref "S33") (pin "3") (pinfunction "S_3") (pintype "passive"))
      (node (ref "S34") (pin "3") (pinfunction "S_3") (pintype "passive"))
      (node (ref "S35") (pin "3") (pinfunction "S_3") (pintype "passive"))
      (node (ref "S36") (pin "3") (pinfunction "S_3") (pintype "passive"))
      (node (ref "S37") (pin "3") (pinfunction "S_3") (pintype "passive"))
      (node (ref "S38") (pin "3") (pinfunction "S_3") (pintype "passive"))
      (node (ref "S39") (pin "3") (pinfunction "S_3") (pintype "passive"))
      (node (ref "S40") (pin "3") (pinfunction "S_3") (pintype "passive"))
      (node (ref "SV2") (pin "3") (pinfunction "3_3") (pintype "passive"))
    )
    (net (code "20") (name "/LINE_10") (class "Default")
      (node (ref "S41") (pin "4") (pinfunction "S1_4") (pintype "passive"))
      (node (ref "S42") (pin "4") (pinfunction "S1_4") (pintype "passive"))
      (node (ref "S43") (pin "4") (pinfunction "S1_4") (pintype "passive"))
      (node (ref "S44") (pin "4") (pinfunction "S1_4") (pintype "passive"))
      (node (ref "S45") (pin "4") (pinfunction "S1_4") (pintype "passive"))
      (node (ref "S46") (pin "4") (pinfunction "S1_4") (pintype "passive"))
      (node (ref "S47") (pin "4") (pinfunction "S1_4") (pintype "passive"))
      (node (ref "S48") (pin "4") (pinfunction "S1_4") (pintype "passive"))
      (node (ref "SV2") (pin "5") (pinfunction "5_5") (pintype "passive"))
    )
    (net (code "21") (name "/LINE_11") (class "Default")
      (node (ref "S41") (pin "3") (pinfunction "S_3") (pintype "passive"))
      (node (ref "S42") (pin "3") (pinfunction "S_3") (pintype "passive"))
      (node (ref "S43") (pin "3") (pinfunction "S_3") (pintype "passive"))
      (node (ref "S44") (pin "3") (pinfunction "S_3") (pintype "passive"))
      (node (ref "S45") (pin "3") (pinfunction "S_3") (pintype "passive"))
      (node (ref "S46") (pin "3") (pinfunction "S_3") (pintype "passive"))
      (node (ref "S47") (pin "3") (pinfunction "S_3") (pintype "passive"))
      (node (ref "S48") (pin "3") (pinfunction "S_3") (pintype "passive"))
      (node (ref "SV2") (pin "7") (pinfunction "7_7") (pintype "passive"))
    )
    (net (code "22") (name "/LINE_12") (class "Default")
      (node (ref "S49") (pin "4") (pinfunction "S1_4") (pintype "passive"))
      (node (ref "S50") (pin "4") (pinfunction "S1_4") (pintype "passive"))
      (node (ref "S51") (pin "4") (pinfunction "S1_4") (pintype "passive"))
      (node (ref "S52") (pin "4") (pinfunction "S1_4") (pintype "passive"))
      (node (ref "S53") (pin "4") (pinfunction "S1_4") (pintype "passive"))
      (node (ref "S54") (pin "4") (pinfunction "S1_4") (pintype "passive"))
      (node (ref "S55") (pin "4") (pinfunction "S1_4") (pintype "passive"))
      (node (ref "S56") (pin "4") (pinfunction "S1_4") (pintype "passive"))
      (node (ref "SV2") (pin "9") (pinfunction "9_9") (pintype "passive"))
    )
    (net (code "23") (name "/LINE_13") (class "Default")
      (node (ref "S49") (pin "3") (pinfunction "S_3") (pintype "passive"))
      (node (ref "S50") (pin "3") (pinfunction "S_3") (pintype "passive"))
      (node (ref "S51") (pin "3") (pinfunction "S_3") (pintype "passive"))
      (node (ref "S52") (pin "3") (pinfunction "S_3") (pintype "passive"))
      (node (ref "S53") (pin "3") (pinfunction "S_3") (pintype "passive"))
      (node (ref "S54") (pin "3") (pinfunction "S_3") (pintype "passive"))
      (node (ref "S55") (pin "3") (pinfunction "S_3") (pintype "passive"))
      (node (ref "S56") (pin "3") (pinfunction "S_3") (pintype "passive"))
      (node (ref "SV2") (pin "11") (pinfunction "11_11") (pintype "passive"))
    )
    (net (code "24") (name "/LINE_14") (class "Default")
      (node (ref "S57") (pin "4") (pinfunction "S1_4") (pintype "passive"))
      (node (ref "S58") (pin "4") (pinfunction "S1_4") (pintype "passive"))
      (node (ref "S59") (pin "4") (pinfunction "S1_4") (pintype "passive"))
      (node (ref "S60") (pin "4") (pinfunction "S1_4") (pintype "passive"))
      (node (ref "S61") (pin "4") (pinfunction "S1_4") (pintype "passive"))
      (node (ref "SV2") (pin "13") (pinfunction "13_13") (pintype "passive"))
    )
    (net (code "25") (name "/LINE_15") (class "Default")
      (node (ref "S57") (pin "3") (pinfunction "S_3") (pintype "passive"))
      (node (ref "S58") (pin "3") (pinfunction "S_3") (pintype "passive"))
      (node (ref "S59") (pin "3") (pinfunction "S_3") (pintype "passive"))
      (node (ref "S60") (pin "3") (pinfunction "S_3") (pintype "passive"))
      (node (ref "S61") (pin "3") (pinfunction "S_3") (pintype "passive"))
      (node (ref "SV2") (pin "15") (pinfunction "15_15") (pintype "passive"))
    )
    (net (code "28") (name "Net-(S1-P)") (class "Default")
      (node (ref "D2") (pin "C") (pinfunction "C_C") (pintype "passive"))
      (node (ref "S1") (pin "1") (pinfunction "P_1") (pintype "passive"))
    )
    (net (code "29") (name "Net-(S1-P1)") (class "Default")
      (node (ref "D1") (pin "C") (pinfunction "C_C") (pintype "passive"))
      (node (ref "S1") (pin "2") (pinfunction "P1_2") (pintype "passive"))
    )
    (net (code "30") (name "Net-(S2-P)") (class "Default")
      (node (ref "D4") (pin "C") (pinfunction "C_C") (pintype "passive"))
      (node (ref "S2") (pin "1") (pinfunction "P_1") (pintype "passive"))
    )
    (net (code "31") (name "Net-(S2-P1)") (class "Default")
      (node (ref "D3") (pin "C") (pinfunction "C_C") (pintype "passive"))
      (node (ref "S2") (pin "2") (pinfunction "P1_2") (pintype "passive"))
    )
    (net (code "32") (name "Net-(S3-P)") (class "Default")
      (node (ref "D6") (pin "C") (pinfunction "C_C") (pintype "passive"))
      (node (ref "S3") (pin "1") (pinfunction "P_1") (pintype "passive"))
    )
    (net (code "33") (name "Net-(S3-P1)") (class "Default")
      (node (ref "D5") (pin "C") (pinfunction "C_C") (pintype "passive"))
      (node (ref "S3") (pin "2") (pinfunction "P1_2") (pintype "passive"))
    )
    (net (code "34") (name "Net-(S4-P)") (class "Default")
      (node (ref "D8") (pin "C") (pinfunction "C_C") (pintype "passive"))
      (node (ref "S4") (pin "1") (pinfunction "P_1") (pintype "passive"))
    )
    (net (code "35") (name "Net-(S4-P1)") (class "Default")
      (node (ref "D7") (pin "C") (pinfunction "C_C") (pintype "passive"))
      (node (ref "S4") (pin "2") (pinfunction "P1_2") (pintype "passive"))
    )
    (net (code "36") (name "Net-(S5-P)") (class "Default")
      (node (ref "D10") (pin "C") (pinfunction "C_C") (pintype "passive"))
      (node (ref "S5") (pin "1") (pinfunction "P_1") (pintype "passive"))
    )
    (net (code "37") (name "Net-(S5-P1)") (class "Default")
      (node (ref "D9") (pin "C") (pinfunction "C_C") (pintype "passive"))
      (node (ref "S5") (pin "2") (pinfunction "P1_2") (pintype "passive"))
    )
    (net (code "38") (name "Net-(S6-P)") (class "Default")
      (node (ref "D12") (pin "C") (pinfunction "C_C") (pintype "passive"))
      (node (ref "S6") (pin "1") (pinfunction "P_1") (pintype "passive"))
    )
    (net (code "39") (name "Net-(S6-P1)") (class "Default")
      (node (ref "D11") (pin "C") (pinfunction "C_C") (pintype "passive"))
      (node (ref "S6") (pin "2") (pinfunction "P1_2") (pintype "passive"))
    )
    (net (code "40") (name "Net-(S7-P)") (class "Default")
      (node (ref "D14") (pin "C") (pinfunction "C_C") (pintype "passive"))
      (node (ref "S7") (pin "1") (pinfunction "P_1") (pintype "passive"))
    )
    (net (code "41") (name "Net-(S7-P1)") (class "Default")
      (node (ref "D13") (pin "C") (pinfunction "C_C") (pintype "passive"))
      (node (ref "S7") (pin "2") (pinfunction "P1_2") (pintype "passive"))
    )
    (net (code "42") (name "Net-(S8-P)") (class "Default")
      (node (ref "D16") (pin "C") (pinfunction "C_C") (pintype "passive"))
      (node (ref "S8") (pin "1") (pinfunction "P_1") (pintype "passive"))
    )
    (net (code "43") (name "Net-(S8-P1)") (class "Default")
      (node (ref "D15") (pin "C") (pinfunction "C_C") (pintype "passive"))
      (node (ref "S8") (pin "2") (pinfunction "P1_2") (pintype "passive"))
    )
    (net (code "44") (name "Net-(S9-P)") (class "Default")
      (node (ref "D20") (pin "C") (pinfunction "C_C") (pintype "passive"))
      (node (ref "S9") (pin "1") (pinfunction "P_1") (pintype "passive"))
    )
    (net (code "45") (name "Net-(S9-P1)") (class "Default")
      (node (ref "D19") (pin "C") (pinfunction "C_C") (pintype "passive"))
      (node (ref "S9") (pin "2") (pinfunction "P1_2") (pintype "passive"))
    )
    (net (code "46") (name "Net-(S10-P)") (class "Default")
      (node (ref "D18") (pin "C") (pinfunction "C_C") (pintype "passive"))
      (node (ref "S10") (pin "1") (pinfunction "P_1") (pintype "passive"))
    )
    (net (code "47") (name "Net-(S10-P1)") (class "Default")
      (node (ref "D17") (pin "C") (pinfunction "C_C") (pintype "passive"))
      (node (ref "S10") (pin "2") (pinfunction "P1_2") (pintype "passive"))
    )
    (net (code "48") (name "Net-(S11-P)") (class "Default")
      (node (ref "D22") (pin "C") (pinfunction "C_C") (pintype "passive"))
      (node (ref "S11") (pin "1") (pinfunction "P_1") (pintype "passive"))
    )
    (net (code "49") (name "Net-(S11-P1)") (class "Default")
      (node (ref "D21") (pin "C") (pinfunction "C_C") (pintype "passive"))
      (node (ref "S11") (pin "2") (pinfunction "P1_2") (pintype "passive"))
    )
    (net (code "50") (name "Net-(S12-P)") (class "Default")
      (node (ref "D24") (pin "C") (pinfunction "C_C") (pintype "passive"))
      (node (ref "S12") (pin "1") (pinfunction "P_1") (pintype "passive"))
    )
    (net (code "51") (name "Net-(S12-P1)") (class "Default")
      (node (ref "D23") (pin "C") (pinfunction "C_C") (pintype "passive"))
      (node (ref "S12") (pin "2") (pinfunction "P1_2") (pintype "passive"))
    )
    (net (code "52") (name "Net-(S13-P)") (class "Default")
      (node (ref "D26") (pin "C") (pinfunction "C_C") (pintype "passive"))
      (node (ref "S13") (pin "1") (pinfunction "P_1") (pintype "passive"))
    )
    (net (code "53") (name "Net-(S13-P1)") (class "Default")
      (node (ref "D25") (pin "C") (pinfunction "C_C") (pintype "passive"))
      (node (ref "S13") (pin "2") (pinfunction "P1_2") (pintype "passive"))
    )
    (net (code "54") (name "Net-(S14-P)") (class "Default")
      (node (ref "D28") (pin "C") (pinfunction "C_C") (pintype "passive"))
      (node (ref "S14") (pin "1") (pinfunction "P_1") (pintype "passive"))
    )
    (net (code "55") (name "Net-(S14-P1)") (class "Default")
      (node (ref "D27") (pin "C") (pinfunction "C_C") (pintype "passive"))
      (node (ref "S14") (pin "2") (pinfunction "P1_2") (pintype "passive"))
    )
    (net (code "56") (name "Net-(S15-P)") (class "Default")
      (node (ref "D30") (pin "C") (pinfunction "C_C") (pintype "passive"))
      (node (ref "S15") (pin "1") (pinfunction "P_1") (pintype "passive"))
    )
    (net (code "57") (name "Net-(S15-P1)") (class "Default")
      (node (ref "D29") (pin "C") (pinfunction "C_C") (pintype "passive"))
      (node (ref "S15") (pin "2") (pinfunction "P1_2") (pintype "passive"))
    )
    (net (code "58") (name "Net-(S16-P)") (class "Default")
      (node (ref "D32") (pin "C") (pinfunction "C_C") (pintype "passive"))
      (node (ref "S16") (pin "1") (pinfunction "P_1") (pintype "passive"))
    )
    (net (code "59") (name "Net-(S16-P1)") (class "Default")
      (node (ref "D31") (pin "C") (pinfunction "C_C") (pintype "passive"))
      (node (ref "S16") (pin "2") (pinfunction "P1_2") (pintype "passive"))
    )
    (net (code "60") (name "Net-(S17-P)") (class "Default")
      (node (ref "D36") (pin "C") (pinfunction "C_C") (pintype "passive"))
      (node (ref "S17") (pin "1") (pinfunction "P_1") (pintype "passive"))
    )
    (net (code "61") (name "Net-(S17-P1)") (class "Default")
      (node (ref "D35") (pin "C") (pinfunction "C_C") (pintype "passive"))
      (node (ref "S17") (pin "2") (pinfunction "P1_2") (pintype "passive"))
    )
    (net (code "62") (name "Net-(S18-P)") (class "Default")
      (node (ref "D34") (pin "C") (pinfunction "C_C") (pintype "passive"))
      (node (ref "S18") (pin "1") (pinfunction "P_1") (pintype "passive"))
    )
    (net (code "63") (name "Net-(S18-P1)") (class "Default")
      (node (ref "D33") (pin "C") (pinfunction "C_C") (pintype "passive"))
      (node (ref "S18") (pin "2") (pinfunction "P1_2") (pintype "passive"))
    )
    (net (code "64") (name "Net-(S19-P)") (class "Default")
      (node (ref "D38") (pin "C") (pinfunction "C_C") (pintype "passive"))
      (node (ref "S19") (pin "1") (pinfunction "P_1") (pintype "passive"))
    )
    (net (code "65") (name "Net-(S19-P1)") (class "Default")
      (node (ref "D37") (pin "C") (pinfunction "C_C") (pintype "passive"))
      (node (ref "S19") (pin "2") (pinfunction "P1_2") (pintype "passive"))
    )
    (net (code "66") (name "Net-(S20-P)") (class "Default")
      (node (ref "D40") (pin "C") (pinfunction "C_C") (pintype "passive"))
      (node (ref "S20") (pin "1") (pinfunction "P_1") (pintype "passive"))
    )
    (net (code "67") (name "Net-(S20-P1)") (class "Default")
      (node (ref "D39") (pin "C") (pinfunction "C_C") (pintype "passive"))
      (node (ref "S20") (pin "2") (pinfunction "P1_2") (pintype "passive"))
    )
    (net (code "68") (name "Net-(S21-P)") (class "Default")
      (node (ref "D42") (pin "C") (pinfunction "C_C") (pintype "passive"))
      (node (ref "S21") (pin "1") (pinfunction "P_1") (pintype "passive"))
    )
    (net (code "69") (name "Net-(S21-P1)") (class "Default")
      (node (ref "D41") (pin "C") (pinfunction "C_C") (pintype "passive"))
      (node (ref "S21") (pin "2") (pinfunction "P1_2") (pintype "passive"))
    )
    (net (code "70") (name "Net-(S22-P)") (class "Default")
      (node (ref "D44") (pin "C") (pinfunction "C_C") (pintype "passive"))
      (node (ref "S22") (pin "1") (pinfunction "P_1") (pintype "passive"))
    )
    (net (code "71") (name "Net-(S22-P1)") (class "Default")
      (node (ref "D43") (pin "C") (pinfunction "C_C") (pintype "passive"))
      (node (ref "S22") (pin "2") (pinfunction "P1_2") (pintype "passive"))
    )
    (net (code "72") (name "Net-(S23-P)") (class "Default")
      (node (ref "D46") (pin "C") (pinfunction "C_C") (pintype "passive"))
      (node (ref "S23") (pin "1") (pinfunction "P_1") (pintype "passive"))
    )
    (net (code "73") (name "Net-(S23-P1)") (class "Default")
      (node (ref "D45") (pin "C") (pinfunction "C_C") (pintype "passive"))
      (node (ref "S23") (pin "2") (pinfunction "P1_2") (pintype "passive"))
    )
    (net (code "74") (name "Net-(S24-P)") (class "Default")
      (node (ref "D48") (pin "C") (pinfunction "C_C") (pintype "passive"))
      (node (ref "S24") (pin "1") (pinfunction "P_1") (pintype "passive"))
    )
    (net (code "75") (name "Net-(S24-P1)") (class "Default")
      (node (ref "D47") (pin "C") (pinfunction "C_C") (pintype "passive"))
      (node (ref "S24") (pin "2") (pinfunction "P1_2") (pintype "passive"))
    )
    (net (code "76") (name "Net-(S25-P)") (class "Default")
      (node (ref "D52") (pin "C") (pinfunction "C_C") (pintype "passive"))
      (node (ref "S25") (pin "1") (pinfunction "P_1") (pintype "passive"))
    )
    (net (code "77") (name "Net-(S25-P1)") (class "Default")
      (node (ref "D51") (pin "C") (pinfunction "C_C") (pintype "passive"))
      (node (ref "S25") (pin "2") (pinfunction "P1_2") (pintype "passive"))
    )
    (net (code "78") (name "Net-(S26-P)") (class "Default")
      (node (ref "D50") (pin "C") (pinfunction "C_C") (pintype "passive"))
      (node (ref "S26") (pin "1") (pinfunction "P_1") (pintype "passive"))
    )
    (net (code "79") (name "Net-(S26-P1)") (class "Default")
      (node (ref "D49") (pin "C") (pinfunction "C_C") (pintype "passive"))
      (node (ref "S26") (pin "2") (pinfunction "P1_2") (pintype "passive"))
    )
    (net (code "80") (name "Net-(S27-P)") (class "Default")
      (node (ref "D54") (pin "C") (pinfunction "C_C") (pintype "passive"))
      (node (ref "S27") (pin "1") (pinfunction "P_1") (pintype "passive"))
    )
    (net (code "81") (name "Net-(S27-P1)") (class "Default")
      (node (ref "D53") (pin "C") (pinfunction "C_C") (pintype "passive"))
      (node (ref "S27") (pin "2") (pinfunction "P1_2") (pintype "passive"))
    )
    (net (code "82") (name "Net-(S28-P)") (class "Default")
      (node (ref "D56") (pin "C") (pinfunction "C_C") (pintype "passive"))
      (node (ref "S28") (pin "1") (pinfunction "P_1") (pintype "passive"))
    )
    (net (code "83") (name "Net-(S28-P1)") (class "Default")
      (node (ref "D55") (pin "C") (pinfunction "C_C") (pintype "passive"))
      (node (ref "S28") (pin "2") (pinfunction "P1_2") (pintype "passive"))
    )
    (net (code "84") (name "Net-(S29-P)") (class "Default")
      (node (ref "D58") (pin "C") (pinfunction "C_C") (pintype "passive"))
      (node (ref "S29") (pin "1") (pinfunction "P_1") (pintype "passive"))
    )
    (net (code "85") (name "Net-(S29-P1)") (class "Default")
      (node (ref "D57") (pin "C") (pinfunction "C_C") (pintype "passive"))
      (node (ref "S29") (pin "2") (pinfunction "P1_2") (pintype "passive"))
    )
    (net (code "86") (name "Net-(S30-P)") (class "Default")
      (node (ref "D60") (pin "C") (pinfunction "C_C") (pintype "passive"))
      (node (ref "S30") (pin "1") (pinfunction "P_1") (pintype "passive"))
    )
    (net (code "87") (name "Net-(S30-P1)") (class "Default")
      (node (ref "D59") (pin "C") (pinfunction "C_C") (pintype "passive"))
      (node (ref "S30") (pin "2") (pinfunction "P1_2") (pintype "passive"))
    )
    (net (code "88") (name "Net-(S31-P)") (class "Default")
      (node (ref "D62") (pin "C") (pinfunction "C_C") (pintype "passive"))
      (node (ref "S31") (pin "1") (pinfunction "P_1") (pintype "passive"))
    )
    (net (code "89") (name "Net-(S31-P1)") (class "Default")
      (node (ref "D61") (pin "C") (pinfunction "C_C") (pintype "passive"))
      (node (ref "S31") (pin "2") (pinfunction "P1_2") (pintype "passive"))
    )
    (net (code "90") (name "Net-(S32-P)") (class "Default")
      (node (ref "D64") (pin "C") (pinfunction "C_C") (pintype "passive"))
      (node (ref "S32") (pin "1") (pinfunction "P_1") (pintype "passive"))
    )
    (net (code "91") (name "Net-(S32-P1)") (class "Default")
      (node (ref "D63") (pin "C") (pinfunction "C_C") (pintype "passive"))
      (node (ref "S32") (pin "2") (pinfunction "P1_2") (pintype "passive"))
    )
    (net (code "92") (name "Net-(S33-P)") (class "Default")
      (node (ref "D66") (pin "C") (pinfunction "C_C") (pintype "passive"))
      (node (ref "S33") (pin "1") (pinfunction "P_1") (pintype "passive"))
    )
    (net (code "93") (name "Net-(S33-P1)") (class "Default")
      (node (ref "D65") (pin "C") (pinfunction "C_C") (pintype "passive"))
      (node (ref "S33") (pin "2") (pinfunction "P1_2") (pintype "passive"))
    )
    (net (code "94") (name "Net-(S34-P)") (class "Default")
      (node (ref "D68") (pin "C") (pinfunction "C_C") (pintype "passive"))
      (node (ref "S34") (pin "1") (pinfunction "P_1") (pintype "passive"))
    )
    (net (code "95") (name "Net-(S34-P1)") (class "Default")
      (node (ref "D67") (pin "C") (pinfunction "C_C") (pintype "passive"))
      (node (ref "S34") (pin "2") (pinfunction "P1_2") (pintype "passive"))
    )
    (net (code "96") (name "Net-(S35-P)") (class "Default")
      (node (ref "D70") (pin "C") (pinfunction "C_C") (pintype "passive"))
      (node (ref "S35") (pin "1") (pinfunction "P_1") (pintype "passive"))
    )
    (net (code "97") (name "Net-(S35-P1)") (class "Default")
      (node (ref "D69") (pin "C") (pinfunction "C_C") (pintype "passive"))
      (node (ref "S35") (pin "2") (pinfunction "P1_2") (pintype "passive"))
    )
    (net (code "98") (name "Net-(S36-P)") (class "Default")
      (node (ref "D72") (pin "C") (pinfunction "C_C") (pintype "passive"))
      (node (ref "S36") (pin "1") (pinfunction "P_1") (pintype "passive"))
    )
    (net (code "99") (name "Net-(S36-P1)") (class "Default")
      (node (ref "D71") (pin "C") (pinfunction "C_C") (pintype "passive"))
      (node (ref "S36") (pin "2") (pinfunction "P1_2") (pintype "passive"))
    )
    (net (code "100") (name "Net-(S37-P)") (class "Default")
      (node (ref "D74") (pin "C") (pinfunction "C_C") (pintype "passive"))
      (node (ref "S37") (pin "1") (pinfunction "P_1") (pintype "passive"))
    )
    (net (code "101") (name "Net-(S37-P1)") (class "Default")
      (node (ref "D73") (pin "C") (pinfunction "C_C") (pintype "passive"))
      (node (ref "S37") (pin "2") (pinfunction "P1_2") (pintype "passive"))
    )
    (net (code "102") (name "Net-(S38-P)") (class "Default")
      (node (ref "D76") (pin "C") (pinfunction "C_C") (pintype "passive"))
      (node (ref "S38") (pin "1") (pinfunction "P_1") (pintype "passive"))
    )
    (net (code "103") (name "Net-(S38-P1)") (class "Default")
      (node (ref "D75") (pin "C") (pinfunction "C_C") (pintype "passive"))
      (node (ref "S38") (pin "2") (pinfunction "P1_2") (pintype "passive"))
    )
    (net (code "104") (name "Net-(S39-P)") (class "Default")
      (node (ref "D78") (pin "C") (pinfunction "C_C") (pintype "passive"))
      (node (ref "S39") (pin "1") (pinfunction "P_1") (pintype "passive"))
    )
    (net (code "105") (name "Net-(S39-P1)") (class "Default")
      (node (ref "D77") (pin "C") (pinfunction "C_C") (pintype "passive"))
      (node (ref "S39") (pin "2") (pinfunction "P1_2") (pintype "passive"))
    )
    (net (code "106") (name "Net-(S40-P)") (class "Default")
      (node (ref "D80") (pin "C") (pinfunction "C_C") (pintype "passive"))
      (node (ref "S40") (pin "1") (pinfunction "P_1") (pintype "passive"))
    )
    (net (code "107") (name "Net-(S40-P1)") (class "Default")
      (node (ref "D79") (pin "C") (pinfunction "C_C") (pintype "passive"))
      (node (ref "S40") (pin "2") (pinfunction "P1_2") (pintype "passive"))
    )
    (net (code "108") (name "Net-(S41-P)") (class "Default")
      (node (ref "D82") (pin "C") (pinfunction "C_C") (pintype "passive"))
      (node (ref "S41") (pin "1") (pinfunction "P_1") (pintype "passive"))
    )
    (net (code "109") (name "Net-(S41-P1)") (class "Default")
      (node (ref "D81") (pin "C") (pinfunction "C_C") (pintype "passive"))
      (node (ref "S41") (pin "2") (pinfunction "P1_2") (pintype "passive"))
    )
    (net (code "110") (name "Net-(S42-P)") (class "Default")
      (node (ref "D84") (pin "C") (pinfunction "C_C") (pintype "passive"))
      (node (ref "S42") (pin "1") (pinfunction "P_1") (pintype "passive"))
    )
    (net (code "111") (name "Net-(S42-P1)") (class "Default")
      (node (ref "D83") (pin "C") (pinfunction "C_C") (pintype "passive"))
      (node (ref "S42") (pin "2") (pinfunction "P1_2") (pintype "passive"))
    )
    (net (code "112") (name "Net-(S43-P)") (class "Default")
      (node (ref "D86") (pin "C") (pinfunction "C_C") (pintype "passive"))
      (node (ref "S43") (pin "1") (pinfunction "P_1") (pintype "passive"))
    )
    (net (code "113") (name "Net-(S43-P1)") (class "Default")
      (node (ref "D85") (pin "C") (pinfunction "C_C") (pintype "passive"))
      (node (ref "S43") (pin "2") (pinfunction "P1_2") (pintype "passive"))
    )
    (net (code "114") (name "Net-(S44-P)") (class "Default")
      (node (ref "D88") (pin "C") (pinfunction "C_C") (pintype "passive"))
      (node (ref "S44") (pin "1") (pinfunction "P_1") (pintype "passive"))
    )
    (net (code "115") (name "Net-(S44-P1)") (class "Default")
      (node (ref "D87") (pin "C") (pinfunction "C_C") (pintype "passive"))
      (node (ref "S44") (pin "2") (pinfunction "P1_2") (pintype "passive"))
    )
    (net (code "116") (name "Net-(S45-P)") (class "Default")
      (node (ref "D90") (pin "C") (pinfunction "C_C") (pintype "passive"))
      (node (ref "S45") (pin "1") (pinfunction "P_1") (pintype "passive"))
    )
    (net (code "117") (name "Net-(S45-P1)") (class "Default")
      (node (ref "D89") (pin "C") (pinfunction "C_C") (pintype "passive"))
      (node (ref "S45") (pin "2") (pinfunction "P1_2") (pintype "passive"))
    )
    (net (code "118") (name "Net-(S46-P)") (class "Default")
      (node (ref "D92") (pin "C") (pinfunction "C_C") (pintype "passive"))
      (node (ref "S46") (pin "1") (pinfunction "P_1") (pintype "passive"))
    )
    (net (code "119") (name "Net-(S46-P1)") (class "Default")
      (node (ref "D91") (pin "C") (pinfunction "C_C") (pintype "passive"))
      (node (ref "S46") (pin "2") (pinfunction "P1_2") (pintype "passive"))
    )
    (net (code "120") (name "Net-(S47-P)") (class "Default")
      (node (ref "D94") (pin "C") (pinfunction "C_C") (pintype "passive"))
      (node (ref "S47") (pin "1") (pinfunction "P_1") (pintype "passive"))
    )
    (net (code "121") (name "Net-(S47-P1)") (class "Default")
      (node (ref "D93") (pin "C") (pinfunction "C_C") (pintype "passive"))
      (node (ref "S47") (pin "2") (pinfunction "P1_2") (pintype "passive"))
    )
    (net (code "122") (name "Net-(S48-P)") (class "Default")
      (node (ref "D96") (pin "C") (pinfunction "C_C") (pintype "passive"))
      (node (ref "S48") (pin "1") (pinfunction "P_1") (pintype "passive"))
    )
    (net (code "123") (name "Net-(S48-P1)") (class "Default")
      (node (ref "D95") (pin "C") (pinfunction "C_C") (pintype "passive"))
      (node (ref "S48") (pin "2") (pinfunction "P1_2") (pintype "passive"))
    )
    (net (code "124") (name "Net-(S49-P)") (class "Default")
      (node (ref "D98") (pin "C") (pinfunction "C_C") (pintype "passive"))
      (node (ref "S49") (pin "1") (pinfunction "P_1") (pintype "passive"))
    )
    (net (code "125") (name "Net-(S49-P1)") (class "Default")
      (node (ref "D97") (pin "C") (pinfunction "C_C") (pintype "passive"))
      (node (ref "S49") (pin "2") (pinfunction "P1_2") (pintype "passive"))
    )
    (net (code "126") (name "Net-(S50-P)") (class "Default")
      (node (ref "D100") (pin "C") (pinfunction "C_C") (pintype "passive"))
      (node (ref "S50") (pin "1") (pinfunction "P_1") (pintype "passive"))
    )
    (net (code "127") (name "Net-(S50-P1)") (class "Default")
      (node (ref "D99") (pin "C") (pinfunction "C_C") (pintype "passive"))
      (node (ref "S50") (pin "2") (pinfunction "P1_2") (pintype "passive"))
    )
    (net (code "128") (name "Net-(S51-P)") (class "Default")
      (node (ref "D102") (pin "C") (pinfunction "C_C") (pintype "passive"))
      (node (ref "S51") (pin "1") (pinfunction "P_1") (pintype "passive"))
    )
    (net (code "129") (name "Net-(S51-P1)") (class "Default")
      (node (ref "D101") (pin "C") (pinfunction "C_C") (pintype "passive"))
      (node (ref "S51") (pin "2") (pinfunction "P1_2") (pintype "passive"))
    )
    (net (code "130") (name "Net-(S52-P)") (class "Default")
      (node (ref "D104") (pin "C") (pinfunction "C_C") (pintype "passive"))
      (node (ref "S52") (pin "1") (pinfunction "P_1") (pintype "passive"))
    )
    (net (code "131") (name "Net-(S52-P1)") (class "Default")
      (node (ref "D103") (pin "C") (pinfunction "C_C") (pintype "passive"))
      (node (ref "S52") (pin "2") (pinfunction "P1_2") (pintype "passive"))
    )
    (net (code "132") (name "Net-(S53-P)") (class "Default")
      (node (ref "D106") (pin "C") (pinfunction "C_C") (pintype "passive"))
      (node (ref "S53") (pin "1") (pinfunction "P_1") (pintype "passive"))
    )
    (net (code "133") (name "Net-(S53-P1)") (class "Default")
      (node (ref "D105") (pin "C") (pinfunction "C_C") (pintype "passive"))
      (node (ref "S53") (pin "2") (pinfunction "P1_2") (pintype "passive"))
    )
    (net (code "134") (name "Net-(S54-P)") (class "Default")
      (node (ref "D108") (pin "C") (pinfunction "C_C") (pintype "passive"))
      (node (ref "S54") (pin "1") (pinfunction "P_1") (pintype "passive"))
    )
    (net (code "135") (name "Net-(S54-P1)") (class "Default")
      (node (ref "D107") (pin "C") (pinfunction "C_C") (pintype "passive"))
      (node (ref "S54") (pin "2") (pinfunction "P1_2") (pintype "passive"))
    )
    (net (code "136") (name "Net-(S55-P)") (class "Default")
      (node (ref "D110") (pin "C") (pinfunction "C_C") (pintype "passive"))
      (node (ref "S55") (pin "1") (pinfunction "P_1") (pintype "passive"))
    )
    (net (code "137") (name "Net-(S55-P1)") (class "Default")
      (node (ref "D109") (pin "C") (pinfunction "C_C") (pintype "passive"))
      (node (ref "S55") (pin "2") (pinfunction "P1_2") (pintype "passive"))
    )
    (net (code "138") (name "Net-(S56-P)") (class "Default")
      (node (ref "D112") (pin "C") (pinfunction "C_C") (pintype "passive"))
      (node (ref "S56") (pin "1") (pinfunction "P_1") (pintype "passive"))
    )
    (net (code "139") (name "Net-(S56-P1)") (class "Default")
      (node (ref "D111") (pin "C") (pinfunction "C_C") (pintype "passive"))
      (node (ref "S56") (pin "2") (pinfunction "P1_2") (pintype "passive"))
    )
    (net (code "140") (name "Net-(S57-P)") (class "Default")
      (node (ref "D114") (pin "C") (pinfunction "C_C") (pintype "passive"))
      (node (ref "S57") (pin "1") (pinfunction "P_1") (pintype "passive"))
    )
    (net (code "141") (name "Net-(S57-P1)") (class "Default")
      (node (ref "D113") (pin "C") (pinfunction "C_C") (pintype "passive"))
      (node (ref "S57") (pin "2") (pinfunction "P1_2") (pintype "passive"))
    )
    (net (code "142") (name "Net-(S58-P)") (class "Default")
      (node (ref "D116") (pin "C") (pinfunction "C_C") (pintype "passive"))
      (node (ref "S58") (pin "1") (pinfunction "P_1") (pintype "passive"))
    )
    (net (code "143") (name "Net-(S58-P1)") (class "Default")
      (node (ref "D115") (pin "C") (pinfunction "C_C") (pintype "passive"))
      (node (ref "S58") (pin "2") (pinfunction "P1_2") (pintype "passive"))
    )
    (net (code "144") (name "Net-(S59-P)") (class "Default")
      (node (ref "D118") (pin "C") (pinfunction "C_C") (pintype "passive"))
      (node (ref "S59") (pin "1") (pinfunction "P_1") (pintype "passive"))
    )
    (net (code "145") (name "Net-(S59-P1)") (class "Default")
      (node (ref "D117") (pin "C") (pinfunction "C_C") (pintype "passive"))
      (node (ref "S59") (pin "2") (pinfunction "P1_2") (pintype "passive"))
    )
    (net (code "146") (name "Net-(S60-P)") (class "Default")
      (node (ref "D120") (pin "C") (pinfunction "C_C") (pintype "passive"))
      (node (ref "S60") (pin "1") (pinfunction "P_1") (pintype "passive"))
    )
    (net (code "147") (name "Net-(S60-P1)") (class "Default")
      (node (ref "D119") (pin "C") (pinfunction "C_C") (pintype "passive"))
      (node (ref "S60") (pin "2") (pinfunction "P1_2") (pintype "passive"))
    )
    (net (code "148") (name "Net-(S61-P)") (class "Default")
      (node (ref "D122") (pin "C") (pinfunction "C_C") (pintype "passive"))
      (node (ref "S61") (pin "1") (pinfunction "P_1") (pintype "passive"))
    )
    (net (code "149") (name "Net-(S61-P1)") (class "Default")
      (node (ref "D121") (pin "C") (pinfunction "C_C") (pintype "passive"))
      (node (ref "S61") (pin "2") (pinfunction "P1_2") (pintype "passive"))
    )
  )
)
